# ELoad_rev0_1.net
KiCad netlist of a schematic drawn in Altium Designer
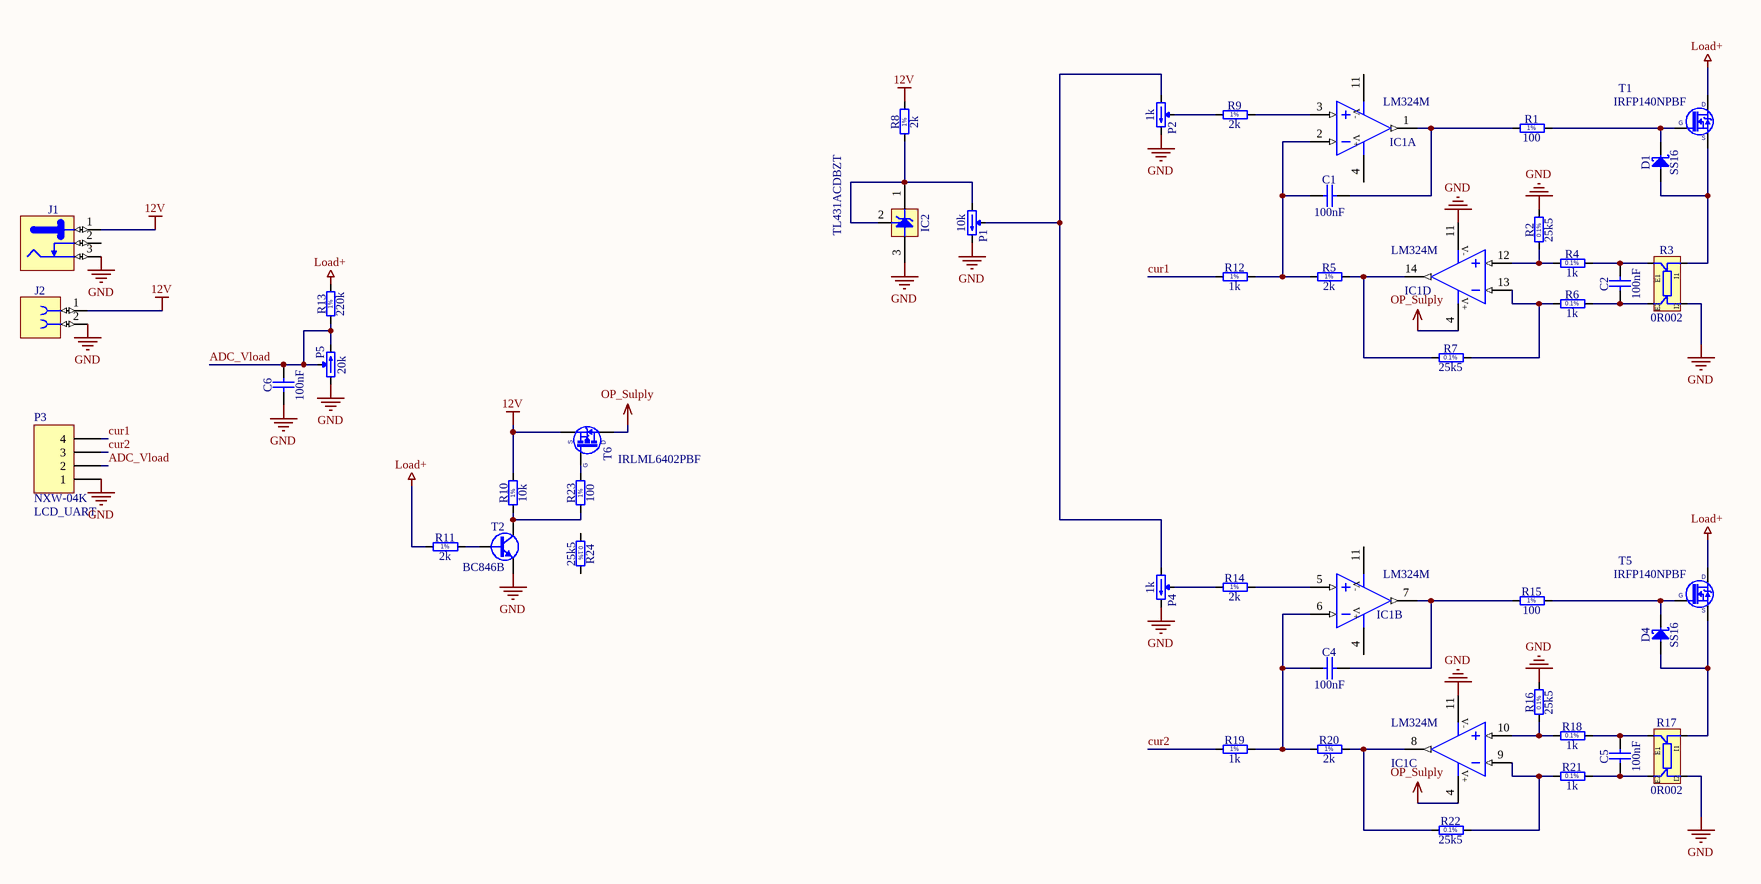
[diagram p0: ELoad_rev0.1.SchDoc]

(export (version "E")
  (design (tool "Eeschema 10.0.6"))
  (components
    (comp (ref "C1")
      (value "100nF")
      (footprint "CAPC2012X135N")
      (description "Non-polarised capacitor")
      (fields
        (field (name "PART NUMBER") "CC0805_100NF_50V_10%_X7R")
        (field (name "VOLTAGE") "50V")
        (field (name "AUTHOR") "CERN DEM JLC")
      )
      (libsource (lib "Capacitors") (part "Capacitor - non polarized"))
    )
    (comp (ref "C2")
      (value "100nF")
      (footprint "CAPC2012X135N")
      (description "Non-polarised capacitor")
      (fields
        (field (name "PART NUMBER") "CC0805_100NF_50V_10%_X7R")
        (field (name "VOLTAGE") "50V")
        (field (name "AUTHOR") "CERN DEM JLC")
      )
      (libsource (lib "Capacitors") (part "Capacitor - non polarized"))
    )
    (comp (ref "C4")
      (value "100nF")
      (footprint "CAPC2012X135N")
      (description "Non-polarised capacitor")
      (fields
        (field (name "PART NUMBER") "CC0805_100NF_50V_10%_X7R")
        (field (name "VOLTAGE") "50V")
        (field (name "AUTHOR") "CERN DEM JLC")
      )
      (libsource (lib "Capacitors") (part "Capacitor - non polarized"))
    )
    (comp (ref "C5")
      (value "100nF")
      (footprint "CAPC2012X135N")
      (description "Non-polarised capacitor")
      (fields
        (field (name "PART NUMBER") "CC0805_100NF_50V_10%_X7R")
        (field (name "VOLTAGE") "50V")
        (field (name "AUTHOR") "CERN DEM JLC")
      )
      (libsource (lib "Capacitors") (part "Capacitor - non polarized"))
    )
    (comp (ref "C6")
      (value "100nF")
      (footprint "CAPC2012X88N")
      (description "Non-polarised capacitor")
      (fields
        (field (name "PART NUMBER") "CC0805_100NF_50V_10%_X7R_YUDEN_UMK212B7104KGH")
        (field (name "VOLTAGE") "50V")
        (field (name "AUTHOR") "CERN DEM JLC")
      )
      (libsource (lib "Capacitors") (part "Capacitor - non polarized"))
    )
    (comp (ref "D1")
      (value "SS16")
      (footprint "DIOM5127X229N")
      (description "Schottky Diode")
      (fields
        (field (name "VOLTAGE") "60V")
        (field (name "POWER") "1A")
        (field (name "AUTHOR") "CERN DEM JLC")
      )
      (libsource (lib "ICs And Semiconductors") (part "Diode Schottky"))
    )
    (comp (ref "D4")
      (value "SS16")
      (footprint "DIOM5127X229N")
      (description "Schottky Diode")
      (fields
        (field (name "VOLTAGE") "60V")
        (field (name "POWER") "1A")
        (field (name "AUTHOR") "CERN DEM JLC")
      )
      (libsource (lib "ICs And Semiconductors") (part "Diode Schottky"))
    )
    (comp (ref "IC1")
      (value "LM324M")
      (footprint "SOIC127P600X175-14N")
      (description "Quad Operational Amplifier")
      (fields (field (name "MANUFACTURER") "FAIRCHILD SEMICONDUCTOR") (field (name "AUTHOR") "CERN DEM JLC"))
      (libsource (lib "ICs And Semiconductors") (part "Operational Amplifier x4 Type1"))
    )
    (comp (ref "IC2")
      (value "TL431ACDBZT")
      (footprint "SOT95P237X112-3N")
      (description "Precision Reference 1=Cathode 2=Adj 3=Anode")
      (fields (field (name "MANUFACTURER") "TEXAS INSTRUMENTS") (field (name "AUTHOR") "CERN DEM JLC"))
      (libsource (lib "ICs And Semiconductors") (part "VREF 1C-2ADJ-3A"))
    )
    (comp (ref "J1")
      (value "Jack")
      (footprint "CLIFF_FC68148(DC-10A)")
      (description "12V /  5A, 2.1mm Diameter Pin, DC Power Socket With  Switch. DC10A Type")
      (fields
        (field (name "PART NUMBER") "CLIFF_FC68148(DC-10A)")
        (field (name "MANUFACTURER") "CLIFF ELECTRONIC COMPONENTS")
        (field (name "AUTHOR") "CERN DEM JLC")
      )
      (libsource (lib "Connectors") (part "CLIFF_FC68148(DC-10A)"))
    )
    (comp (ref "J2")
      (value "~")
      (footprint "PHOENIX_1792863")
      (description "Connector 2 Female")
      (fields
        (field (name "PART NUMBER") "PHOENIX_1792863")
        (field (name "MANUFACTURER") "PHOENIX CONTACT")
        (field (name "AUTHOR") "CERN DEM JLC")
      )
      (libsource (lib "Connectors") (part "Connector 2 Female"))
    )
    (comp (ref "P1")
      (value "10k")
      (footprint "5390:3590S")
      (description "Trimming Potentiometer")
      (fields
        (field (name "PART NUMBER") "TRIM_25T_10K_BOURNS_3296Y-1-103LF")
        (field (name "POWER") "0.5W")
        (field (name "AUTHOR") "CERN DEM JLC")
      )
      (libsource (lib "Resistors") (part "Trimming Potentiometer"))
    )
    (comp (ref "P2")
      (value "1k")
      (footprint "TRIM_BOURNS_3290W")
      (description "Trimming Potentiometer")
      (fields
        (field (name "PART NUMBER") "TRIM_25T_1K_BOURNS_3290W-1-102")
        (field (name "POWER") "1W")
        (field (name "AUTHOR") "CERN DEM MR")
      )
      (libsource (lib "Resistors") (part "Trimming Potentiometer"))
    )
    (comp (ref "P3")
      (value "NXW-04K")
      (footprint "NX:NXW-04K")
      (description "Header, 4-Pin")
      (fields (field (name "PARAMETER 1") "LCD_UART") (field (name "PUBLISHER") "Altium Limited"))
      (libsource (lib "Miscellaneous Connectors") (part "Header 4"))
    )
    (comp (ref "P4")
      (value "1k")
      (footprint "TRIM_BOURNS_3290W")
      (description "Trimming Potentiometer")
      (fields
        (field (name "PART NUMBER") "TRIM_25T_1K_BOURNS_3290W-1-102")
        (field (name "POWER") "1W")
        (field (name "AUTHOR") "CERN DEM MR")
      )
      (libsource (lib "Resistors") (part "Trimming Potentiometer"))
    )
    (comp (ref "P5")
      (value "20k")
      (footprint "TRIM_BOURNS_3290W")
      (description "Trimming Potentiometer")
      (fields
        (field (name "PART NUMBER") "TRIM_25T_20K_BOURNS_3290W-1-203")
        (field (name "POWER") "1W")
        (field (name "AUTHOR") "CERN DEM BC")
      )
      (libsource (lib "Resistors") (part "Trimming Potentiometer"))
    )
    (comp (ref "R1")
      (value "100")
      (footprint "RESC2012X60N")
      (description "Resistor - 1%")
      (fields
        (field (name "PART NUMBER") "R0805_100R_1%_0.125W_100PPM")
        (field (name "POWER") "0.125W")
        (field (name "AUTHOR") "CERN DEM JLC")
      )
      (libsource (lib "Resistors") (part "Resistor - 1%"))
    )
    (comp (ref "R2")
      (value "25k5")
      (footprint "RESC2012X60N")
      (description "Resistor - 0.1%")
      (fields
        (field (name "PART NUMBER") "R0805_25K5_0.1%_0.1W_10PPM")
        (field (name "POWER") "0.1W")
        (field (name "AUTHOR") "CERN DEM JLC")
      )
      (libsource (lib "Resistors") (part "Resistor - 0.1%"))
    )
    (comp (ref "R3")
      (value "0R002")
      (footprint "RES_VISHAY_WSK2512_0R005-0R2")
      (description "Power and Current Sensing Resistor")
      (fields
        (field (name "PART NUMBER") "R2512_0R002_1%_1W_35PPM_VISHAY_WSK2512")
        (field (name "POWER") "1W")
        (field (name "AUTHOR") "CERN DEM MR")
      )
      (libsource (lib "Resistors") (part "Current Sense Resistor"))
    )
    (comp (ref "R4")
      (value "1k")
      (footprint "RESC2012X60N")
      (description "Resistor - 0.1%")
      (fields
        (field (name "PART NUMBER") "R0805_1K_0.1%_0.125W_25PPM")
        (field (name "POWER") "0.125W")
        (field (name "AUTHOR") "CERN DEM JLC")
      )
      (libsource (lib "Resistors") (part "Resistor - 0.1%"))
    )
    (comp (ref "R5")
      (value "2k")
      (footprint "RESC2012X60N")
      (description "Resistor - 1%")
      (fields
        (field (name "PART NUMBER") "R0805_2K_1%_0.125W_100PPM")
        (field (name "POWER") "0.125W")
        (field (name "AUTHOR") "CERN DEM JLC")
      )
      (libsource (lib "Resistors") (part "Resistor - 1%"))
    )
    (comp (ref "R6")
      (value "1k")
      (footprint "RESC2012X60N")
      (description "Resistor - 0.1%")
      (fields
        (field (name "PART NUMBER") "R0805_1K_0.1%_0.125W_25PPM")
        (field (name "POWER") "0.125W")
        (field (name "AUTHOR") "CERN DEM JLC")
      )
      (libsource (lib "Resistors") (part "Resistor - 0.1%"))
    )
    (comp (ref "R7")
      (value "25k5")
      (footprint "RESC2012X60N")
      (description "Resistor - 0.1%")
      (fields
        (field (name "PART NUMBER") "R0805_25K5_0.1%_0.1W_10PPM")
        (field (name "POWER") "0.1W")
        (field (name "AUTHOR") "CERN DEM JLC")
      )
      (libsource (lib "Resistors") (part "Resistor - 0.1%"))
    )
    (comp (ref "R8")
      (value "2k")
      (footprint "RESC2012X60N")
      (description "Resistor - 1%")
      (fields
        (field (name "PART NUMBER") "R0805_2K_1%_0.125W_100PPM")
        (field (name "POWER") "0.125W")
        (field (name "AUTHOR") "CERN DEM JLC")
      )
      (libsource (lib "Resistors") (part "Resistor - 1%"))
    )
    (comp (ref "R9")
      (value "2k")
      (footprint "RESC2012X60N")
      (description "Resistor - 1%")
      (fields
        (field (name "PART NUMBER") "R0805_2K_1%_0.125W_100PPM")
        (field (name "POWER") "0.125W")
        (field (name "AUTHOR") "CERN DEM JLC")
      )
      (libsource (lib "Resistors") (part "Resistor - 1%"))
    )
    (comp (ref "R10")
      (value "10k")
      (footprint "RESC2012X60N")
      (description "Resistor - 1%")
      (fields
        (field (name "PART NUMBER") "R0805_10K_1%_0.125W_100PPM")
        (field (name "POWER") "0.125W")
        (field (name "AUTHOR") "CERN DEM JLC")
      )
      (libsource (lib "Resistors") (part "Resistor - 1%"))
    )
    (comp (ref "R11")
      (value "2k")
      (footprint "RESC2012X60N")
      (description "Resistor - 1%")
      (fields
        (field (name "PART NUMBER") "R0805_2K_1%_0.125W_100PPM")
        (field (name "POWER") "0.125W")
        (field (name "AUTHOR") "CERN DEM JLC")
      )
      (libsource (lib "Resistors") (part "Resistor - 1%"))
    )
    (comp (ref "R12")
      (value "1k")
      (footprint "RESC2012X60N")
      (description "Resistor - 1%")
      (fields
        (field (name "PART NUMBER") "R0805_1K_1%_0.125W_100PPM")
        (field (name "POWER") "0.125W")
        (field (name "AUTHOR") "CERN DEM JLC")
      )
      (libsource (lib "Resistors") (part "Resistor - 1%"))
    )
    (comp (ref "R13")
      (value "220k")
      (footprint "RESC2012X60N")
      (description "Resistor - 1%")
      (fields
        (field (name "PART NUMBER") "R0805_220K_1%_0.125W_100PPM")
        (field (name "POWER") "0.125W")
        (field (name "AUTHOR") "CERN DEM JLC")
      )
      (libsource (lib "Resistors") (part "Resistor - 1%"))
    )
    (comp (ref "R14")
      (value "2k")
      (footprint "RESC2012X60N")
      (description "Resistor - 1%")
      (fields
        (field (name "PART NUMBER") "R0805_2K_1%_0.125W_100PPM")
        (field (name "POWER") "0.125W")
        (field (name "AUTHOR") "CERN DEM JLC")
      )
      (libsource (lib "Resistors") (part "Resistor - 1%"))
    )
    (comp (ref "R15")
      (value "100")
      (footprint "RESC2012X60N")
      (description "Resistor - 1%")
      (fields
        (field (name "PART NUMBER") "R0805_100R_1%_0.125W_100PPM")
        (field (name "POWER") "0.125W")
        (field (name "AUTHOR") "CERN DEM JLC")
      )
      (libsource (lib "Resistors") (part "Resistor - 1%"))
    )
    (comp (ref "R16")
      (value "25k5")
      (footprint "RESC2012X60N")
      (description "Resistor - 0.1%")
      (fields
        (field (name "PART NUMBER") "R0805_25K5_0.1%_0.1W_10PPM")
        (field (name "POWER") "0.1W")
        (field (name "AUTHOR") "CERN DEM JLC")
      )
      (libsource (lib "Resistors") (part "Resistor - 0.1%"))
    )
    (comp (ref "R17")
      (value "0R002")
      (footprint "RES_VISHAY_WSK2512_0R005-0R2")
      (description "Power and Current Sensing Resistor")
      (fields
        (field (name "PART NUMBER") "R2512_0R002_1%_1W_35PPM_VISHAY_WSK2512")
        (field (name "POWER") "1W")
        (field (name "AUTHOR") "CERN DEM MR")
      )
      (libsource (lib "Resistors") (part "Current Sense Resistor"))
    )
    (comp (ref "R18")
      (value "1k")
      (footprint "RESC2012X60N")
      (description "Resistor - 0.1%")
      (fields
        (field (name "PART NUMBER") "R0805_1K_0.1%_0.125W_25PPM")
        (field (name "POWER") "0.125W")
        (field (name "AUTHOR") "CERN DEM JLC")
      )
      (libsource (lib "Resistors") (part "Resistor - 0.1%"))
    )
    (comp (ref "R19")
      (value "1k")
      (footprint "RESC2012X60N")
      (description "Resistor - 1%")
      (fields
        (field (name "PART NUMBER") "R0805_1K_1%_0.125W_100PPM")
        (field (name "POWER") "0.125W")
        (field (name "AUTHOR") "CERN DEM JLC")
      )
      (libsource (lib "Resistors") (part "Resistor - 1%"))
    )
    (comp (ref "R20")
      (value "2k")
      (footprint "RESC2012X60N")
      (description "Resistor - 1%")
      (fields
        (field (name "PART NUMBER") "R0805_2K_1%_0.125W_100PPM")
        (field (name "POWER") "0.125W")
        (field (name "AUTHOR") "CERN DEM JLC")
      )
      (libsource (lib "Resistors") (part "Resistor - 1%"))
    )
    (comp (ref "R21")
      (value "1k")
      (footprint "RESC2012X60N")
      (description "Resistor - 0.1%")
      (fields
        (field (name "PART NUMBER") "R0805_1K_0.1%_0.125W_25PPM")
        (field (name "POWER") "0.125W")
        (field (name "AUTHOR") "CERN DEM JLC")
      )
      (libsource (lib "Resistors") (part "Resistor - 0.1%"))
    )
    (comp (ref "R22")
      (value "25k5")
      (footprint "RESC2012X60N")
      (description "Resistor - 0.1%")
      (fields
        (field (name "PART NUMBER") "R0805_25K5_0.1%_0.1W_10PPM")
        (field (name "POWER") "0.1W")
        (field (name "AUTHOR") "CERN DEM JLC")
      )
      (libsource (lib "Resistors") (part "Resistor - 0.1%"))
    )
    (comp (ref "R23")
      (value "100")
      (footprint "RESC2012X60N")
      (description "Resistor - 1%")
      (fields
        (field (name "PART NUMBER") "R0805_100R_1%_0.125W_100PPM")
        (field (name "POWER") "0.125W")
        (field (name "AUTHOR") "CERN DEM JLC")
      )
      (libsource (lib "Resistors") (part "Resistor - 1%"))
    )
    (comp (ref "R24")
      (value "25k5")
      (footprint "RESC2012X60N")
      (description "Resistor - 0.1%")
      (fields
        (field (name "PART NUMBER") "R0805_25K5_0.1%_0.1W_10PPM")
        (field (name "POWER") "0.1W")
        (field (name "AUTHOR") "CERN DEM JLC")
      )
      (libsource (lib "Resistors") (part "Resistor - 0.1%"))
    )
    (comp (ref "T1")
      (value "IRFP140NPBF")
      (footprint "TO-247AC-v")
      (description "N-CHANNEL MOSFET WITH ZENER DIODE")
      (fields
        (field (name "PART NUMBER") "IRFP140NPBF_v")
        (field (name "MANUFACTURER") "INTERNATIONAL RECTIFIER")
        (field (name "AUTHOR") "CERN DEM JLC")
      )
      (libsource (lib "ICs And Semiconductors") (part "N-MOSFET-DZ 1G 2D 3S"))
    )
    (comp (ref "T2")
      (value "BC846B")
      (footprint "SOT95P230X110-3N")
      (description "NPN Transistor")
      (fields (field (name "MANUFACTURER") "NXP SEMICONDUCTORS") (field (name "AUTHOR") "CERN DEM JLC"))
      (libsource (lib "ICs And Semiconductors") (part "NPN B1 E2 C3"))
    )
    (comp (ref "T5")
      (value "IRFP140NPBF")
      (footprint "TO-247AC-v")
      (description "N-CHANNEL MOSFET WITH ZENER DIODE")
      (fields
        (field (name "PART NUMBER") "IRFP140NPBF_v")
        (field (name "MANUFACTURER") "INTERNATIONAL RECTIFIER")
        (field (name "AUTHOR") "CERN DEM JLC")
      )
      (libsource (lib "ICs And Semiconductors") (part "N-MOSFET-DZ 1G 2D 3S"))
    )
    (comp (ref "T6")
      (value "IRLML6402PBF")
      (footprint "SOT95P237X112-3N")
      (description "P-CHANNEL MOSFET WITH ZENER DIODE")
      (fields (field (name "MANUFACTURER") "INTERNATIONAL RECTIFIER") (field (name "AUTHOR") "CERN DEM JLC"))
      (libsource (lib "ICs And Semiconductors") (part "P-MOSFET-DZ 1G 2S 3D"))
    )
  )
  (nets
    (net (code "1") (name "/ADC_Vload") (class "Default")
      (node (ref "C6") (pin "2") (pinfunction "2_2") (pintype "passive"))
      (node (ref "P3") (pin "2") (pinfunction "2_2") (pintype "passive"))
      (node (ref "P5") (pin "2") (pinfunction "W_2") (pintype "passive"))
      (node (ref "P5") (pin "3") (pinfunction "CW_3") (pintype "passive"))
      (node (ref "R13") (pin "1") (pinfunction "1_1") (pintype "passive"))
    )
    (net (code "2") (name "/cur1") (class "Default")
      (node (ref "P3") (pin "4") (pinfunction "4_4") (pintype "passive"))
      (node (ref "R12") (pin "1") (pinfunction "1_1") (pintype "passive"))
    )
    (net (code "3") (name "/cur2") (class "Default")
      (node (ref "P3") (pin "3") (pinfunction "3_3") (pintype "passive"))
      (node (ref "R19") (pin "1") (pinfunction "1_1") (pintype "passive"))
    )
    (net (code "4") (name "12V") (class "Default")
      (node (ref "J1") (pin "1") (pinfunction "1_1") (pintype "bidirectional"))
      (node (ref "J2") (pin "1") (pinfunction "1_1") (pintype "bidirectional"))
      (node (ref "R10") (pin "2") (pinfunction "2_2") (pintype "passive"))
      (node (ref "R8") (pin "2") (pinfunction "2_2") (pintype "passive"))
      (node (ref "T6") (pin "2") (pinfunction "S_2") (pintype "passive"))
    )
    (net (code "5") (name "GND") (class "Default")
      (node (ref "C6") (pin "1") (pinfunction "1_1") (pintype "passive"))
      (node (ref "IC1") (pin "11") (pinfunction "V-_11") (pintype "power_in"))
      (node (ref "IC2") (pin "3") (pinfunction "A_3") (pintype "passive"))
      (node (ref "J1") (pin "3") (pinfunction "3_3") (pintype "bidirectional"))
      (node (ref "J2") (pin "2") (pinfunction "2_2") (pintype "bidirectional"))
      (node (ref "P1") (pin "3") (pinfunction "CW_3") (pintype "passive"))
      (node (ref "P2") (pin "3") (pinfunction "CW_3") (pintype "passive"))
      (node (ref "P3") (pin "1") (pinfunction "1_1") (pintype "passive"))
      (node (ref "P4") (pin "3") (pinfunction "CW_3") (pintype "passive"))
      (node (ref "P5") (pin "1") (pinfunction "CCW_1") (pintype "passive"))
      (node (ref "R16") (pin "2") (pinfunction "2_2") (pintype "passive"))
      (node (ref "R17") (pin "I2") (pinfunction "I2_I2") (pintype "passive"))
      (node (ref "R2") (pin "2") (pinfunction "2_2") (pintype "passive"))
      (node (ref "R3") (pin "I2") (pinfunction "I2_I2") (pintype "passive"))
      (node (ref "T2") (pin "2") (pinfunction "E_2") (pintype "passive"))
    )
    (net (code "6") (name "Load+") (class "Default")
      (node (ref "R11") (pin "1") (pinfunction "1_1") (pintype "passive"))
      (node (ref "R13") (pin "2") (pinfunction "2_2") (pintype "passive"))
      (node (ref "T1") (pin "2") (pinfunction "D_2") (pintype "passive"))
      (node (ref "T5") (pin "2") (pinfunction "D_2") (pintype "passive"))
    )
    (net (code "7") (name "Net-(C2-Pad1)") (class "Default")
      (node (ref "C2") (pin "1") (pinfunction "1_1") (pintype "passive"))
      (node (ref "R3") (pin "E2") (pinfunction "E2_E2") (pintype "passive"))
      (node (ref "R6") (pin "2") (pinfunction "2_2") (pintype "passive"))
    )
    (net (code "8") (name "Net-(C2-Pad2)") (class "Default")
      (node (ref "C2") (pin "2") (pinfunction "2_2") (pintype "passive"))
      (node (ref "R3") (pin "E1") (pinfunction "E1_E1") (pintype "passive"))
      (node (ref "R4") (pin "2") (pinfunction "2_2") (pintype "passive"))
    )
    (net (code "9") (name "Net-(C5-Pad1)") (class "Default")
      (node (ref "C5") (pin "1") (pinfunction "1_1") (pintype "passive"))
      (node (ref "R17") (pin "E2") (pinfunction "E2_E2") (pintype "passive"))
      (node (ref "R21") (pin "2") (pinfunction "2_2") (pintype "passive"))
    )
    (net (code "10") (name "Net-(C5-Pad2)") (class "Default")
      (node (ref "C5") (pin "2") (pinfunction "2_2") (pintype "passive"))
      (node (ref "R17") (pin "E1") (pinfunction "E1_E1") (pintype "passive"))
      (node (ref "R18") (pin "2") (pinfunction "2_2") (pintype "passive"))
    )
    (net (code "11") (name "Net-(D1-A)") (class "Default")
      (node (ref "D1") (pin "2") (pinfunction "A_2") (pintype "passive"))
      (node (ref "R3") (pin "I1") (pinfunction "I1_I1") (pintype "passive"))
      (node (ref "T1") (pin "3") (pinfunction "S_3") (pintype "passive"))
    )
    (net (code "12") (name "Net-(D1-C)") (class "Default")
      (node (ref "D1") (pin "1") (pinfunction "C_1") (pintype "passive"))
      (node (ref "R1") (pin "2") (pinfunction "2_2") (pintype "passive"))
      (node (ref "T1") (pin "1") (pinfunction "G_1") (pintype "passive"))
    )
    (net (code "13") (name "Net-(D4-A)") (class "Default")
      (node (ref "D4") (pin "2") (pinfunction "A_2") (pintype "passive"))
      (node (ref "R17") (pin "I1") (pinfunction "I1_I1") (pintype "passive"))
      (node (ref "T5") (pin "3") (pinfunction "S_3") (pintype "passive"))
    )
    (net (code "14") (name "Net-(D4-C)") (class "Default")
      (node (ref "D4") (pin "1") (pinfunction "C_1") (pintype "passive"))
      (node (ref "R15") (pin "2") (pinfunction "2_2") (pintype "passive"))
      (node (ref "T5") (pin "1") (pinfunction "G_1") (pintype "passive"))
    )
    (net (code "15") (name "Net-(IC1A-IN+)") (class "Default")
      (node (ref "IC1") (pin "3") (pinfunction "IN+_3") (pintype "input"))
      (node (ref "R9") (pin "2") (pinfunction "2_2") (pintype "passive"))
    )
    (net (code "16") (name "Net-(IC1A-IN-)") (class "Default")
      (node (ref "C1") (pin "1") (pinfunction "1_1") (pintype "passive"))
      (node (ref "IC1") (pin "2") (pinfunction "IN-_2") (pintype "input"))
      (node (ref "R12") (pin "2") (pinfunction "2_2") (pintype "passive"))
      (node (ref "R5") (pin "1") (pinfunction "1_1") (pintype "passive"))
    )
    (net (code "17") (name "Net-(IC1A-OUT)") (class "Default")
      (node (ref "C1") (pin "2") (pinfunction "2_2") (pintype "passive"))
      (node (ref "IC1") (pin "1") (pinfunction "OUT_1") (pintype "output"))
      (node (ref "R1") (pin "1") (pinfunction "1_1") (pintype "passive"))
    )
    (net (code "18") (name "Net-(IC1B-IN+)") (class "Default")
      (node (ref "IC1") (pin "5") (pinfunction "IN+_5") (pintype "input"))
      (node (ref "R14") (pin "2") (pinfunction "2_2") (pintype "passive"))
    )
    (net (code "19") (name "Net-(IC1B-IN-)") (class "Default")
      (node (ref "C4") (pin "1") (pinfunction "1_1") (pintype "passive"))
      (node (ref "IC1") (pin "6") (pinfunction "IN-_6") (pintype "input"))
      (node (ref "R19") (pin "2") (pinfunction "2_2") (pintype "passive"))
      (node (ref "R20") (pin "1") (pinfunction "1_1") (pintype "passive"))
    )
    (net (code "20") (name "Net-(IC1B-OUT)") (class "Default")
      (node (ref "C4") (pin "2") (pinfunction "2_2") (pintype "passive"))
      (node (ref "IC1") (pin "7") (pinfunction "OUT_7") (pintype "output"))
      (node (ref "R15") (pin "1") (pinfunction "1_1") (pintype "passive"))
    )
    (net (code "21") (name "Net-(IC1C-IN+)") (class "Default")
      (node (ref "IC1") (pin "10") (pinfunction "IN+_10") (pintype "input"))
      (node (ref "R16") (pin "1") (pinfunction "1_1") (pintype "passive"))
      (node (ref "R18") (pin "1") (pinfunction "1_1") (pintype "passive"))
    )
    (net (code "22") (name "Net-(IC1C-IN-)") (class "Default")
      (node (ref "IC1") (pin "9") (pinfunction "IN-_9") (pintype "input"))
      (node (ref "R21") (pin "1") (pinfunction "1_1") (pintype "passive"))
      (node (ref "R22") (pin "2") (pinfunction "2_2") (pintype "passive"))
    )
    (net (code "23") (name "Net-(IC1C-OUT)") (class "Default")
      (node (ref "IC1") (pin "8") (pinfunction "OUT_8") (pintype "output"))
      (node (ref "R20") (pin "2") (pinfunction "2_2") (pintype "passive"))
      (node (ref "R22") (pin "1") (pinfunction "1_1") (pintype "passive"))
    )
    (net (code "24") (name "Net-(IC1D-IN+)") (class "Default")
      (node (ref "IC1") (pin "12") (pinfunction "IN+_12") (pintype "input"))
      (node (ref "R2") (pin "1") (pinfunction "1_1") (pintype "passive"))
      (node (ref "R4") (pin "1") (pinfunction "1_1") (pintype "passive"))
    )
    (net (code "25") (name "Net-(IC1D-IN-)") (class "Default")
      (node (ref "IC1") (pin "13") (pinfunction "IN-_13") (pintype "input"))
      (node (ref "R6") (pin "1") (pinfunction "1_1") (pintype "passive"))
      (node (ref "R7") (pin "2") (pinfunction "2_2") (pintype "passive"))
    )
    (net (code "26") (name "Net-(IC1D-OUT)") (class "Default")
      (node (ref "IC1") (pin "14") (pinfunction "OUT_14") (pintype "output"))
      (node (ref "R5") (pin "2") (pinfunction "2_2") (pintype "passive"))
      (node (ref "R7") (pin "1") (pinfunction "1_1") (pintype "passive"))
    )
    (net (code "27") (name "Net-(IC2-Adj)") (class "Default")
      (node (ref "IC2") (pin "1") (pinfunction "C_1") (pintype "passive"))
      (node (ref "IC2") (pin "2") (pinfunction "Adj_2") (pintype "passive"))
      (node (ref "P1") (pin "1") (pinfunction "CCW_1") (pintype "passive"))
      (node (ref "R8") (pin "1") (pinfunction "1_1") (pintype "passive"))
    )
    (net (code "28") (name "Net-(P1-W)") (class "Default")
      (node (ref "P1") (pin "2") (pinfunction "W_2") (pintype "passive"))
      (node (ref "P2") (pin "1") (pinfunction "CCW_1") (pintype "passive"))
      (node (ref "P4") (pin "1") (pinfunction "CCW_1") (pintype "passive"))
    )
    (net (code "29") (name "Net-(P2-W)") (class "Default")
      (node (ref "P2") (pin "2") (pinfunction "W_2") (pintype "passive"))
      (node (ref "R9") (pin "1") (pinfunction "1_1") (pintype "passive"))
    )
    (net (code "30") (name "Net-(P4-W)") (class "Default")
      (node (ref "P4") (pin "2") (pinfunction "W_2") (pintype "passive"))
      (node (ref "R14") (pin "1") (pinfunction "1_1") (pintype "passive"))
    )
    (net (code "31") (name "Net-(T2-B)") (class "Default")
      (node (ref "R11") (pin "2") (pinfunction "2_2") (pintype "passive"))
      (node (ref "T2") (pin "1") (pinfunction "B_1") (pintype "passive"))
    )
    (net (code "32") (name "Net-(T2-C)") (class "Default")
      (node (ref "R10") (pin "1") (pinfunction "1_1") (pintype "passive"))
      (node (ref "R23") (pin "1") (pinfunction "1_1") (pintype "passive"))
      (node (ref "T2") (pin "3") (pinfunction "C_3") (pintype "passive"))
    )
    (net (code "33") (name "Net-(T6-G)") (class "Default")
      (node (ref "R23") (pin "2") (pinfunction "2_2") (pintype "passive"))
      (node (ref "T6") (pin "1") (pinfunction "G_1") (pintype "passive"))
    )
    (net (code "34") (name "OP_Sulply") (class "Default")
      (node (ref "IC1") (pin "4") (pinfunction "V+_4") (pintype "power_in"))
      (node (ref "T6") (pin "3") (pinfunction "D_3") (pintype "passive"))
    )
    (net (code "35") (name "unconnected-(IC1A-V+-Pad4)") (class "Default")
      (node (ref "IC1") (pin "4") (pinfunction "V+_4") (pintype "power_in"))
    )
    (net (code "36") (name "unconnected-(IC1A-V--Pad11)") (class "Default")
      (node (ref "IC1") (pin "11") (pinfunction "V-_11") (pintype "power_in"))
    )
    (net (code "37") (name "unconnected-(IC1B-V+-Pad4)") (class "Default")
      (node (ref "IC1") (pin "4") (pinfunction "V+_4") (pintype "power_in"))
    )
    (net (code "38") (name "unconnected-(IC1B-V--Pad11)") (class "Default")
      (node (ref "IC1") (pin "11") (pinfunction "V-_11") (pintype "power_in"))
    )
    (net (code "39") (name "unconnected-(J1-Pad2)") (class "Default")
      (node (ref "J1") (pin "2") (pinfunction "2_2") (pintype "bidirectional"))
    )
    (net (code "40") (name "unconnected-(R24-Pad1)") (class "Default")
      (node (ref "R24") (pin "1") (pinfunction "1_1") (pintype "passive"))
    )
    (net (code "41") (name "unconnected-(R24-Pad2)") (class "Default")
      (node (ref "R24") (pin "2") (pinfunction "2_2") (pintype "passive"))
    )
  )
)
